# LM2596_Sheet1.net
KiCad netlist of a schematic drawn in Altium Designer
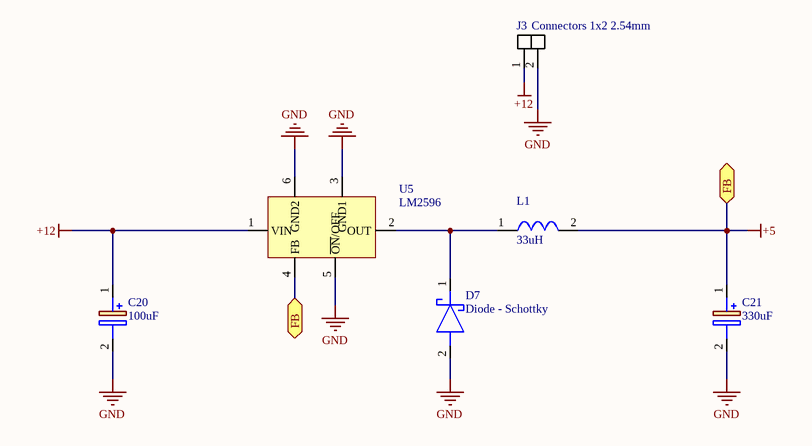
[diagram p0: LM2596_Sheet1.SchDoc]

(export (version "E")
  (design (tool "Eeschema 10.0.6"))
  (components
    (comp (ref "C20")
      (value "100uF")
      (footprint "CAPP_Lytic_D_6.6")
      (description "Capacitor Polarised")
      (libsource (lib "Faydali_Yuk_Schlib1") (part "Cap - Pol"))
    )
    (comp (ref "C21")
      (value "330uF")
      (footprint "CAPP_Lytic_D_6.6")
      (description "Capacitor Polarised")
      (libsource (lib "Faydali_Yuk_Schlib1") (part "Cap - Pol"))
    )
    (comp (ref "D7")
      (value "Diode - Schottky")
      (footprint "DO214AB (SMC)")
      (description "Schottky Diode")
      (libsource (lib "Faydali_Yuk_Schlib1") (part "Diode - Schottky"))
    )
    (comp (ref "J3")
      (value "Connectors 1x2 2.54mm")
      (footprint "Connectors 1x2 2.54mm")
      (description "2 Pin (1x2) 2.54mm Erkek Pin Header THT")
      (libsource (lib "Faydali_Yuk_Schlib1") (part "Connectors 1x2 2.54mm"))
    )
    (comp (ref "L1")
      (value "33uH")
      (footprint "INDUCTOR  - 12X12 SMD")
      (description "SRI1204-330M - INDUCTOR POWER 33UH 12X12X5MM SMD")
      (libsource (lib "Faydali_Yuk_Schlib1") (part "INDUCTOR 33uH"))
    )
    (comp (ref "U5")
      (value "LM2596")
      (footprint "TO263-5 (D2PAK-5) - LM2596R-5.0-HTC")
      (description "LM2596R-5.0-HTC - IC-2596 V.REG.3A 5V STEP-DOWN TO-263-5L")
      (libsource (lib "Faydali_Yuk_Schlib1") (part "LM2596"))
    )
  )
  (nets
    (net (code "1") (name "+5") (class "Default")
      (node (ref "C21") (pin "1") (pinfunction "+_1") (pintype "passive"))
      (node (ref "L1") (pin "2") (pinfunction "2_2") (pintype "passive"))
      (node (ref "U5") (pin "4") (pinfunction "FB_4") (pintype "passive"))
    )
    (net (code "2") (name "+12") (class "Default")
      (node (ref "C20") (pin "1") (pinfunction "+_1") (pintype "passive"))
      (node (ref "J3") (pin "1") (pinfunction "1_1") (pintype "passive"))
      (node (ref "U5") (pin "1") (pinfunction "VIN_1") (pintype "passive"))
    )
    (net (code "3") (name "GND") (class "Default")
      (node (ref "C20") (pin "2") (pinfunction "-_2") (pintype "passive"))
      (node (ref "C21") (pin "2") (pinfunction "-_2") (pintype "passive"))
      (node (ref "D7") (pin "2") (pinfunction "A_2") (pintype "passive"))
      (node (ref "J3") (pin "2") (pinfunction "2_2") (pintype "passive"))
      (node (ref "U5") (pin "3") (pinfunction "GND1_3") (pintype "passive"))
      (node (ref "U5") (pin "5") (pinfunction "~{ON}/OFF_5") (pintype "passive"))
      (node (ref "U5") (pin "6") (pinfunction "GND2_6") (pintype "passive"))
    )
    (net (code "4") (name "Net-(D7-K)") (class "Default")
      (node (ref "D7") (pin "1") (pinfunction "K_1") (pintype "passive"))
      (node (ref "L1") (pin "1") (pinfunction "1_1") (pintype "passive"))
      (node (ref "U5") (pin "2") (pinfunction "OUT_2") (pintype "passive"))
    )
  )
)
